# HMI.net
KiCad netlist of a schematic drawn in Altium Designer
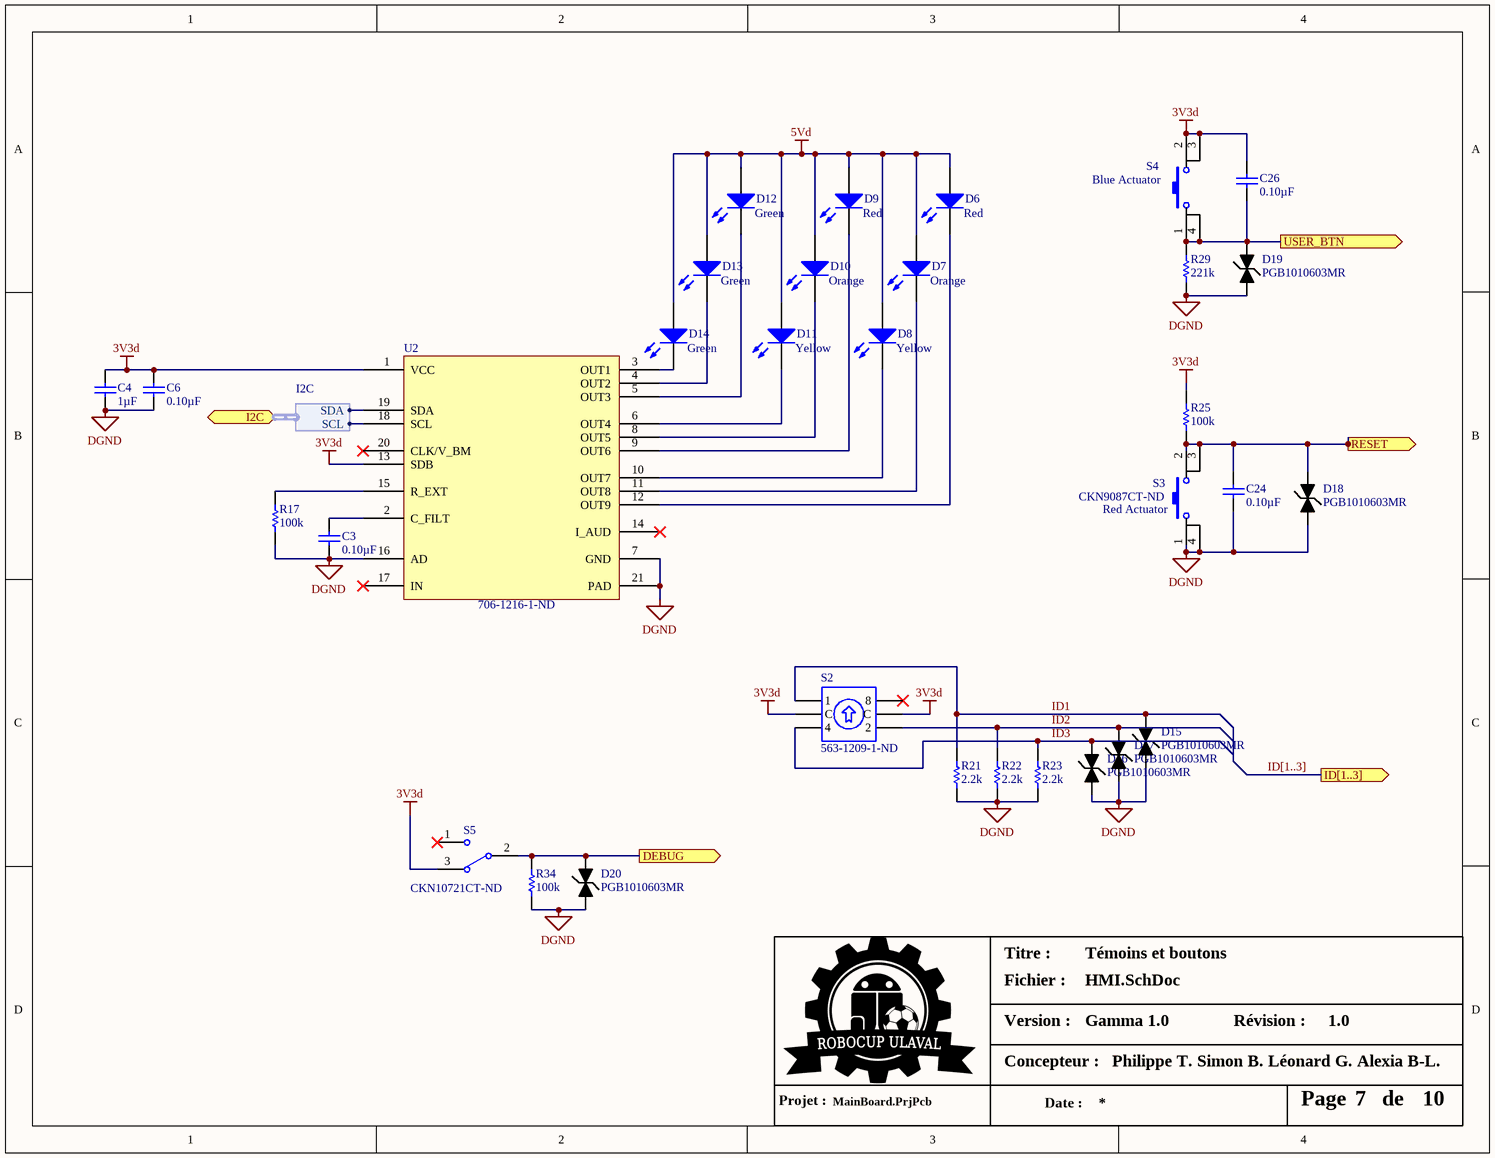
[diagram p0: HMI.SchDoc]

(export (version "E")
  (design (tool "Eeschema 10.0.6"))
  (components
    (comp (ref "C3")
      (value "CL10B104KB8SFNC")
      (footprint "0603")
      (description "CAP CER 0.1UF 50V X7R 0603")
      (fields
        (field (name "MANUFACTURER") "Samsung Electro-Mechanics America, Inc.")
        (field (name "TOLERANCE") "±10%")
        (field (name "CAPACITANCE") "0.10µF")
      )
      (libsource (lib "ResCap") (part "CL10B104KB8SFNC"))
    )
    (comp (ref "C4")
      (value "CL21B105KBFNFNE")
      (footprint "0805")
      (description "CAP CER 1UF 50V X7R 0805")
      (fields
        (field (name "MANUFACTURER") "Samsung Electro-Mechanics America, Inc.")
        (field (name "TOLERANCE") "±10%")
        (field (name "CAPACITANCE") "1µF")
      )
      (libsource (lib "ResCap") (part "CL21B105KBFNFNE"))
    )
    (comp (ref "C6")
      (value "CL10B104KB8SFNC")
      (footprint "0603")
      (description "CAP CER 0.1UF 50V X7R 0603")
      (fields
        (field (name "MANUFACTURER") "Samsung Electro-Mechanics America, Inc.")
        (field (name "TOLERANCE") "±10%")
        (field (name "CAPACITANCE") "0.10µF")
      )
      (libsource (lib "ResCap") (part "CL10B104KB8SFNC"))
    )
    (comp (ref "C24")
      (value "CL10B104KB8SFNC")
      (footprint "0603")
      (description "CAP CER 0.1UF 50V X7R 0603")
      (fields
        (field (name "MANUFACTURER") "Samsung Electro-Mechanics America, Inc.")
        (field (name "TOLERANCE") "±10%")
        (field (name "CAPACITANCE") "0.10µF")
      )
      (libsource (lib "ResCap") (part "CL10B104KB8SFNC"))
    )
    (comp (ref "C26")
      (value "CL10B104KB8SFNC")
      (footprint "0603")
      (description "CAP CER 0.1UF 50V X7R 0603")
      (fields
        (field (name "MANUFACTURER") "Samsung Electro-Mechanics America, Inc.")
        (field (name "TOLERANCE") "±10%")
        (field (name "CAPACITANCE") "0.10µF")
      )
      (libsource (lib "ResCap") (part "CL10B104KB8SFNC"))
    )
    (comp (ref "D6")
      (value "LH R974-LP-1")
      (footprint "0805")
      (description "LED RED DIFFUSED 0805 SMD")
      (fields (field (name "MANUFACTURER") "OSRAM Opto Semiconductors Inc.") (field (name "COLOR") "Red"))
      (libsource (lib "MainBoard") (part "LH R974-LP-1"))
    )
    (comp (ref "D7")
      (value "AA1112H-TR")
      (footprint "0805")
      (description "LED ORANGE DIFFUSED 0805 SMD")
      (fields (field (name "MANUFACTURER") "Stanley Electric Co") (field (name "COLOR") "Orange"))
      (libsource (lib "MainBoard") (part "AA1112H-TR"))
    )
    (comp (ref "D8")
      (value "LY R976-PS-36")
      (footprint "0805")
      (description "LED YELLOW DIFFUSED 0805 SMD")
      (fields (field (name "MANUFACTURER") "OSRAM Opto Semiconductors Inc.") (field (name "COLOR") "Yellow"))
      (libsource (lib "MainBoard") (part "LY R976-PS-36"))
    )
    (comp (ref "D9")
      (value "LH R974-LP-1")
      (footprint "0805")
      (description "LED RED DIFFUSED 0805 SMD")
      (fields (field (name "MANUFACTURER") "OSRAM Opto Semiconductors Inc.") (field (name "COLOR") "Red"))
      (libsource (lib "MainBoard") (part "LH R974-LP-1"))
    )
    (comp (ref "D10")
      (value "AA1112H-TR")
      (footprint "0805")
      (description "LED ORANGE DIFFUSED 0805 SMD")
      (fields (field (name "MANUFACTURER") "Stanley Electric Co") (field (name "COLOR") "Orange"))
      (libsource (lib "MainBoard") (part "AA1112H-TR"))
    )
    (comp (ref "D11")
      (value "LY R976-PS-36")
      (footprint "0805")
      (description "LED YELLOW DIFFUSED 0805 SMD")
      (fields (field (name "MANUFACTURER") "OSRAM Opto Semiconductors Inc.") (field (name "COLOR") "Yellow"))
      (libsource (lib "MainBoard") (part "LY R976-PS-36"))
    )
    (comp (ref "D12")
      (value "LG R971-KN-1")
      (footprint "0805")
      (description "LED GREEN DIFFUSED 0805 SMD")
      (fields (field (name "MANUFACTURER") "OSRAM Opto Semiconductors Inc.") (field (name "COLOR") "Green"))
      (libsource (lib "MainBoard") (part "LG R971-KN-1"))
    )
    (comp (ref "D13")
      (value "LG R971-KN-1")
      (footprint "0805")
      (description "LED GREEN DIFFUSED 0805 SMD")
      (fields (field (name "MANUFACTURER") "OSRAM Opto Semiconductors Inc.") (field (name "COLOR") "Green"))
      (libsource (lib "MainBoard") (part "LG R971-KN-1"))
    )
    (comp (ref "D14")
      (value "LG R971-KN-1")
      (footprint "0805")
      (description "LED GREEN DIFFUSED 0805 SMD")
      (fields (field (name "MANUFACTURER") "OSRAM Opto Semiconductors Inc.") (field (name "COLOR") "Green"))
      (libsource (lib "MainBoard") (part "LG R971-KN-1"))
    )
    (comp (ref "D15")
      (value "PGB1010603MR")
      (footprint "0603")
      (description "TVS DIODE 24VWM 150VC 0603")
      (libsource (lib "MainBoard") (part "PGB1010603MR"))
    )
    (comp (ref "D16")
      (value "PGB1010603MR")
      (footprint "0603")
      (description "TVS DIODE 24VWM 150VC 0603")
      (libsource (lib "MainBoard") (part "PGB1010603MR"))
    )
    (comp (ref "D17")
      (value "PGB1010603MR")
      (footprint "0603")
      (description "TVS DIODE 24VWM 150VC 0603")
      (libsource (lib "MainBoard") (part "PGB1010603MR"))
    )
    (comp (ref "D18")
      (value "PGB1010603MR")
      (footprint "0603")
      (description "TVS DIODE 24VWM 150VC 0603")
      (libsource (lib "MainBoard") (part "PGB1010603MR"))
    )
    (comp (ref "D19")
      (value "PGB1010603MR")
      (footprint "0603")
      (description "TVS DIODE 24VWM 150VC 0603")
      (libsource (lib "MainBoard") (part "PGB1010603MR"))
    )
    (comp (ref "D20")
      (value "PGB1010603MR")
      (footprint "0603")
      (description "TVS DIODE 24VWM 150VC 0603")
      (libsource (lib "MainBoard") (part "PGB1010603MR"))
    )
    (comp (ref "R17")
      (value "RC0603JR-07100KL")
      (footprint "0603")
      (description "RES SMD 100K OHM 5% 1/10W 0603")
      (fields
        (field (name "MANUFACTURER") "Yageo")
        (field (name "TOLERANCE") "±5%")
        (field (name "RESISTANCE (OHMS)") "100k")
      )
      (libsource (lib "ResCap") (part "RC0603JR-07100KL"))
    )
    (comp (ref "R21")
      (value "RC0603FR-072K2L")
      (footprint "0603")
      (description "RES SMD 2.2K OHM 1% 1/10W 0603")
      (fields
        (field (name "MANUFACTURER") "Yageo")
        (field (name "TOLERANCE") "±1%")
        (field (name "RESISTANCE (OHMS)") "2.2k")
      )
      (libsource (lib "ResCap") (part "RC0603FR-072K2L"))
    )
    (comp (ref "R22")
      (value "RC0603FR-072K2L")
      (footprint "0603")
      (description "RES SMD 2.2K OHM 1% 1/10W 0603")
      (fields
        (field (name "MANUFACTURER") "Yageo")
        (field (name "TOLERANCE") "±1%")
        (field (name "RESISTANCE (OHMS)") "2.2k")
      )
      (libsource (lib "ResCap") (part "RC0603FR-072K2L"))
    )
    (comp (ref "R23")
      (value "RC0603FR-072K2L")
      (footprint "0603")
      (description "RES SMD 2.2K OHM 1% 1/10W 0603")
      (fields
        (field (name "MANUFACTURER") "Yageo")
        (field (name "TOLERANCE") "±1%")
        (field (name "RESISTANCE (OHMS)") "2.2k")
      )
      (libsource (lib "ResCap") (part "RC0603FR-072K2L"))
    )
    (comp (ref "R25")
      (value "RC0603JR-07100KL")
      (footprint "0603")
      (description "RES SMD 100K OHM 5% 1/10W 0603")
      (fields
        (field (name "MANUFACTURER") "Yageo")
        (field (name "TOLERANCE") "±5%")
        (field (name "RESISTANCE (OHMS)") "100k")
      )
      (libsource (lib "ResCap") (part "RC0603JR-07100KL"))
    )
    (comp (ref "R29")
      (value "RC0603FR-07221KL")
      (footprint "0603")
      (description "RES SMD 221K OHM 1% 1/10W 0603")
      (fields
        (field (name "MANUFACTURER") "Yageo")
        (field (name "TOLERANCE") "±1%")
        (field (name "RESISTANCE (OHMS)") "221k")
      )
      (libsource (lib "ResCap") (part "RC0603FR-07221KL"))
    )
    (comp (ref "R34")
      (value "RC0603JR-07100KL")
      (footprint "0603")
      (description "RES SMD 100K OHM 5% 1/10W 0603")
      (fields
        (field (name "MANUFACTURER") "Yageo")
        (field (name "TOLERANCE") "±5%")
        (field (name "RESISTANCE (OHMS)") "100k")
      )
      (libsource (lib "ResCap") (part "RC0603JR-07100KL"))
    )
    (comp (ref "S2")
      (value "SH-7010TB")
      (footprint "RotarySwitch")
      (description "SWITCH ROTARY DIP BCD 100MA 5V")
      (fields
        (field (name "MANUFACTURER") "Copal Electronics Inc.")
        (field (name "SUPPLIER PART NUMBER 1") "563-1209-1-ND")
      )
      (libsource (lib "MainBoard") (part "SH-7010TB"))
    )
    (comp (ref "S3")
      (value "PTS645SK50SMTR92 LFS")
      (footprint "6 mm Tact Switches")
      (description "SWITCH TACTILE SPST-NO 0.05A 12V")
      (fields
        (field (name "MANUFACTURER") "C&K Components")
        (field (name "SUPPLIER PART NUMBER 1") "CKN9087CT-ND")
        (field (name "FEATURES") "Red Actuator")
      )
      (libsource (lib "MainBoard") (part "PTS645SK50SMTR92 LFS"))
    )
    (comp (ref "S4")
      (value "PTS645SM43SMTR92 LFS")
      (footprint "6 mm Tact Switches")
      (description "SWITCH TACTILE SPST-NO 0.05A 12V")
      (fields (field (name "MANUFACTURER") "C&K Components") (field (name "FEATURES") "Blue Actuator"))
      (libsource (lib "design3") (part "PTS645SM43SMTR92 LFS"))
    )
    (comp (ref "S5")
      (value "JS102011JCQN")
      (footprint "SPDT-SW")
      (description "SWITCH SLIDE SPDT 300MA 6V")
      (fields
        (field (name "MANUFACTURER") "C&K Components")
        (field (name "SUPPLIER PART NUMBER 1") "CKN10721CT-ND")
      )
      (libsource (lib "MainBoard") (part "JS102011JCQN"))
    )
    (comp (ref "U2")
      (value "IS31FL3199-QFLS2-TR")
      (footprint "QFN40P300X300X80_HS-21N")
      (description "IC LED DRIVER LIN DIM 40MA 20QFN")
      (fields
        (field (name "MANUFACTURER") "ISSI, Integrated Silicon Solution Inc")
        (field (name "SUPPLIER PART NUMBER 1") "706-1216-1-ND")
      )
      (libsource (lib "MainBoard") (part "IS31FL3199-QFLS2-TR"))
    )
  )
  (nets
    (net (code "2") (name "/DEBUG") (class "Default")
      (node (ref "D20") (pin "2") (pintype "passive"))
      (node (ref "R34") (pin "2") (pinfunction "2_2") (pintype "passive"))
      (node (ref "S5") (pin "2") (pinfunction "2_2") (pintype "passive"))
    )
    (net (code "3") (name "/ID1") (class "Default")
      (node (ref "D15") (pin "2") (pintype "passive"))
      (node (ref "R21") (pin "2") (pinfunction "2_2") (pintype "passive"))
      (node (ref "S2") (pin "1") (pinfunction "1_1") (pintype "passive"))
    )
    (net (code "4") (name "/ID2") (class "Default")
      (node (ref "D17") (pin "2") (pintype "passive"))
      (node (ref "R22") (pin "2") (pinfunction "2_2") (pintype "passive"))
      (node (ref "S2") (pin "4") (pinfunction "2_4") (pintype "passive"))
    )
    (net (code "5") (name "/ID3") (class "Default")
      (node (ref "D16") (pin "2") (pintype "passive"))
      (node (ref "R23") (pin "2") (pinfunction "2_2") (pintype "passive"))
      (node (ref "S2") (pin "3") (pinfunction "4_3") (pintype "passive"))
    )
    (net (code "7") (name "/RESET") (class "Default")
      (node (ref "C24") (pin "2") (pinfunction "2_2") (pintype "passive"))
      (node (ref "D18") (pin "2") (pintype "passive"))
      (node (ref "R25") (pin "1") (pinfunction "1_1") (pintype "passive"))
      (node (ref "S3") (pin "2") (pinfunction "2_2") (pintype "passive"))
      (node (ref "S3") (pin "3") (pinfunction "3_3") (pintype "passive"))
    )
    (net (code "8") (name "/SCL") (class "Default")
      (node (ref "U2") (pin "18") (pinfunction "SCL_18") (pintype "passive"))
    )
    (net (code "9") (name "/SDA") (class "Default")
      (node (ref "U2") (pin "19") (pinfunction "SDA_19") (pintype "passive"))
    )
    (net (code "10") (name "/USER_BTN") (class "Default")
      (node (ref "C26") (pin "1") (pinfunction "1_1") (pintype "passive"))
      (node (ref "D19") (pin "2") (pintype "passive"))
      (node (ref "R29") (pin "2") (pinfunction "2_2") (pintype "passive"))
      (node (ref "S4") (pin "1") (pinfunction "1_1") (pintype "passive"))
      (node (ref "S4") (pin "4") (pinfunction "4_4") (pintype "passive"))
    )
    (net (code "12") (name "3V3d") (class "Default")
      (node (ref "C26") (pin "2") (pinfunction "2_2") (pintype "passive"))
      (node (ref "C4") (pin "2") (pinfunction "2_2") (pintype "passive"))
      (node (ref "C6") (pin "2") (pinfunction "2_2") (pintype "passive"))
      (node (ref "R25") (pin "2") (pinfunction "2_2") (pintype "passive"))
      (node (ref "S2") (pin "2") (pinfunction "C_2") (pintype "passive"))
      (node (ref "S2") (pin "5") (pinfunction "C_5") (pintype "passive"))
      (node (ref "S4") (pin "2") (pinfunction "2_2") (pintype "passive"))
      (node (ref "S4") (pin "3") (pinfunction "3_3") (pintype "passive"))
      (node (ref "S5") (pin "3") (pinfunction "3_3") (pintype "passive"))
      (node (ref "U2") (pin "1") (pinfunction "VCC_1") (pintype "passive"))
      (node (ref "U2") (pin "13") (pinfunction "SDB_13") (pintype "passive"))
    )
    (net (code "13") (name "5Vd") (class "Default")
      (node (ref "D10") (pin "1") (pinfunction "A_1") (pintype "passive"))
      (node (ref "D11") (pin "1") (pinfunction "A_1") (pintype "passive"))
      (node (ref "D12") (pin "1") (pinfunction "A_1") (pintype "passive"))
      (node (ref "D13") (pin "1") (pinfunction "A_1") (pintype "passive"))
      (node (ref "D14") (pin "1") (pinfunction "A_1") (pintype "passive"))
      (node (ref "D6") (pin "1") (pinfunction "A_1") (pintype "passive"))
      (node (ref "D7") (pin "1") (pinfunction "A_1") (pintype "passive"))
      (node (ref "D8") (pin "1") (pinfunction "A_1") (pintype "passive"))
      (node (ref "D9") (pin "1") (pinfunction "A_1") (pintype "passive"))
    )
    (net (code "14") (name "DGND") (class "Default")
      (node (ref "C24") (pin "1") (pinfunction "1_1") (pintype "passive"))
      (node (ref "C3") (pin "1") (pinfunction "1_1") (pintype "passive"))
      (node (ref "C4") (pin "1") (pinfunction "1_1") (pintype "passive"))
      (node (ref "C6") (pin "1") (pinfunction "1_1") (pintype "passive"))
      (node (ref "D15") (pin "1") (pintype "passive"))
      (node (ref "D16") (pin "1") (pintype "passive"))
      (node (ref "D17") (pin "1") (pintype "passive"))
      (node (ref "D18") (pin "1") (pintype "passive"))
      (node (ref "D19") (pin "1") (pintype "passive"))
      (node (ref "D20") (pin "1") (pintype "passive"))
      (node (ref "R17") (pin "1") (pinfunction "1_1") (pintype "passive"))
      (node (ref "R21") (pin "1") (pinfunction "1_1") (pintype "passive"))
      (node (ref "R22") (pin "1") (pinfunction "1_1") (pintype "passive"))
      (node (ref "R23") (pin "1") (pinfunction "1_1") (pintype "passive"))
      (node (ref "R29") (pin "1") (pinfunction "1_1") (pintype "passive"))
      (node (ref "R34") (pin "1") (pinfunction "1_1") (pintype "passive"))
      (node (ref "S3") (pin "1") (pinfunction "1_1") (pintype "passive"))
      (node (ref "S3") (pin "4") (pinfunction "4_4") (pintype "passive"))
      (node (ref "U2") (pin "16") (pinfunction "AD_16") (pintype "passive"))
      (node (ref "U2") (pin "21") (pinfunction "PAD_21") (pintype "passive"))
      (node (ref "U2") (pin "7") (pinfunction "GND_7") (pintype "passive"))
    )
    (net (code "15") (name "Net-(D6-K)") (class "Default")
      (node (ref "D6") (pin "2") (pinfunction "K_2") (pintype "passive"))
      (node (ref "U2") (pin "12") (pinfunction "OUT9_12") (pintype "passive"))
    )
    (net (code "16") (name "Net-(D7-K)") (class "Default")
      (node (ref "D7") (pin "2") (pinfunction "K_2") (pintype "passive"))
      (node (ref "U2") (pin "11") (pinfunction "OUT8_11") (pintype "passive"))
    )
    (net (code "17") (name "Net-(D8-K)") (class "Default")
      (node (ref "D8") (pin "2") (pinfunction "K_2") (pintype "passive"))
      (node (ref "U2") (pin "10") (pinfunction "OUT7_10") (pintype "passive"))
    )
    (net (code "18") (name "Net-(D9-K)") (class "Default")
      (node (ref "D9") (pin "2") (pinfunction "K_2") (pintype "passive"))
      (node (ref "U2") (pin "9") (pinfunction "OUT6_9") (pintype "passive"))
    )
    (net (code "19") (name "Net-(D10-K)") (class "Default")
      (node (ref "D10") (pin "2") (pinfunction "K_2") (pintype "passive"))
      (node (ref "U2") (pin "8") (pinfunction "OUT5_8") (pintype "passive"))
    )
    (net (code "20") (name "Net-(D11-K)") (class "Default")
      (node (ref "D11") (pin "2") (pinfunction "K_2") (pintype "passive"))
      (node (ref "U2") (pin "6") (pinfunction "OUT4_6") (pintype "passive"))
    )
    (net (code "21") (name "Net-(D12-K)") (class "Default")
      (node (ref "D12") (pin "2") (pinfunction "K_2") (pintype "passive"))
      (node (ref "U2") (pin "5") (pinfunction "OUT3_5") (pintype "passive"))
    )
    (net (code "22") (name "Net-(D13-K)") (class "Default")
      (node (ref "D13") (pin "2") (pinfunction "K_2") (pintype "passive"))
      (node (ref "U2") (pin "4") (pinfunction "OUT2_4") (pintype "passive"))
    )
    (net (code "23") (name "Net-(D14-K)") (class "Default")
      (node (ref "D14") (pin "2") (pinfunction "K_2") (pintype "passive"))
      (node (ref "U2") (pin "3") (pinfunction "OUT1_3") (pintype "passive"))
    )
    (net (code "24") (name "Net-(U2-C_FILT)") (class "Default")
      (node (ref "C3") (pin "2") (pinfunction "2_2") (pintype "passive"))
      (node (ref "U2") (pin "2") (pinfunction "C_FILT_2") (pintype "passive"))
    )
    (net (code "25") (name "Net-(U2-R_EXT)") (class "Default")
      (node (ref "R17") (pin "2") (pinfunction "2_2") (pintype "passive"))
      (node (ref "U2") (pin "15") (pinfunction "R_EXT_15") (pintype "passive"))
    )
    (net (code "26") (name "unconnected-(S2-8-Pad6)") (class "Default")
      (node (ref "S2") (pin "6") (pinfunction "8_6") (pintype "passive+no_connect"))
    )
    (net (code "27") (name "unconnected-(S5-Pad1)") (class "Default")
      (node (ref "S5") (pin "1") (pinfunction "1_1") (pintype "passive+no_connect"))
    )
    (net (code "28") (name "unconnected-(U2-CLK{slash}V_BM-Pad20)") (class "Default")
      (node (ref "U2") (pin "20") (pinfunction "CLK/V_BM_20") (pintype "passive+no_connect"))
    )
    (net (code "29") (name "unconnected-(U2-IN-Pad17)") (class "Default")
      (node (ref "U2") (pin "17") (pinfunction "IN_17") (pintype "passive+no_connect"))
    )
    (net (code "30") (name "unconnected-(U2-I_AUD-Pad14)") (class "Default")
      (node (ref "U2") (pin "14") (pinfunction "I_AUD_14") (pintype "passive+no_connect"))
    )
  )
)
